# main.net
KiCad netlist of a schematic drawn in EAGLE
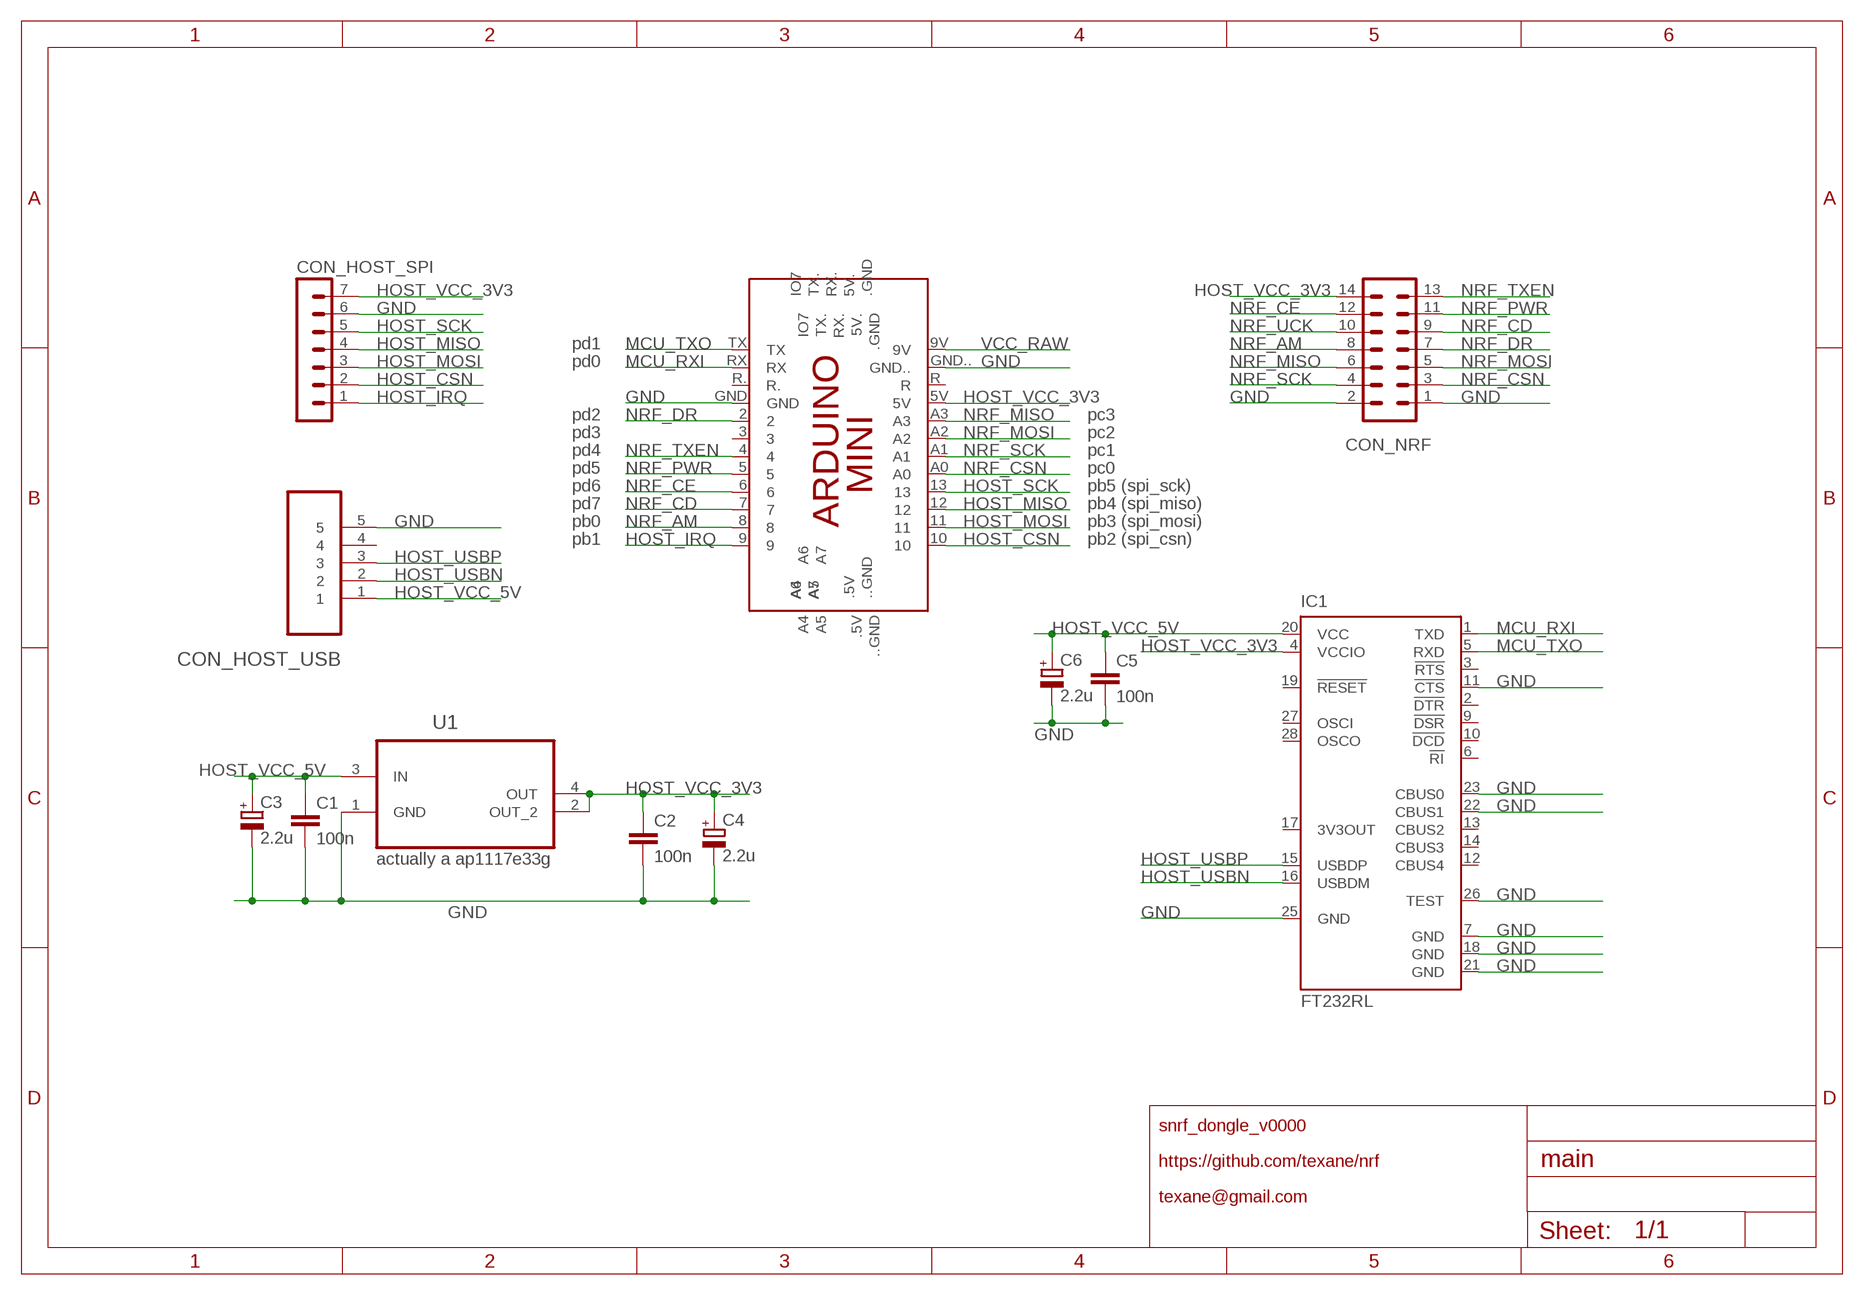
[diagram p0: schematic, sheet 1]

(export (version "E")
  (design (tool "Eeschema 10.0.6"))
  (components
    (comp (ref "C1")
      (value "100n")
      (footprint "eagle-import:C1206K")
      (libsource (lib "eagle-import") (part "C-EUC1206K"))
    )
    (comp (ref "C2")
      (value "100n")
      (footprint "eagle-import:C1206K")
      (libsource (lib "eagle-import") (part "C-EUC1206K"))
    )
    (comp (ref "C3")
      (value "2.2u")
      (footprint "eagle-import:A_3216-18W")
      (libsource (lib "eagle-import") (part "CPOL-EUA/3216-18W"))
    )
    (comp (ref "C4")
      (value "2.2u")
      (footprint "eagle-import:A_3216-18W")
      (libsource (lib "eagle-import") (part "CPOL-EUA/3216-18W"))
    )
    (comp (ref "C5")
      (value "100n")
      (footprint "eagle-import:C1206K")
      (libsource (lib "eagle-import") (part "C-EUC1206K"))
    )
    (comp (ref "C6")
      (value "2.2u")
      (footprint "eagle-import:A_3216-18W")
      (libsource (lib "eagle-import") (part "CPOL-EUA/3216-18W"))
    )
    (comp (ref "CON_HOST_SPI")
      (value "MA07-1")
      (footprint "eagle-import:MA07-1")
      (libsource (lib "eagle-import") (part "MA07-1"))
    )
    (comp (ref "CON_HOST_USB")
      (value "47346-0001")
      (footprint "eagle-import:MOLEX_47346-0001")
      (libsource (lib "eagle-import") (part "47346-0001"))
    )
    (comp (ref "CON_NRF")
      (value "MA07-2")
      (footprint "eagle-import:MA07-2")
      (libsource (lib "eagle-import") (part "MA07-2"))
    )
    (comp (ref "IC1")
      (value "FT232RL")
      (footprint "eagle-import:SSOP28")
      (libsource (lib "eagle-import") (part "FT232RL"))
    )
    (comp (ref "PCB1")
      (value "ARDUINO_MINI")
      (footprint "eagle-import:ARDUINO_MINI")
      (libsource (lib "eagle-import") (part "ARDUINO_MINI"))
    )
    (comp (ref "U1")
      (value "LDO33")
      (footprint "eagle-import:SOT230P700X180-4N")
      (fields (field (name "MPN") "ADP3338AKCZ-2.5RL7"))
      (libsource (lib "eagle-import") (part "ADP3338AKCZ-2.5RL7"))
    )
  )
  (nets
    (net (code "1") (name "/GND") (class "Default")
      (node (ref "C1") (pin "2") (pinfunction "2_2") (pintype "passive"))
      (node (ref "C2") (pin "2") (pinfunction "2_2") (pintype "passive"))
      (node (ref "C3") (pin "-") (pinfunction "-_-") (pintype "passive"))
      (node (ref "C4") (pin "-") (pinfunction "-_-") (pintype "passive"))
      (node (ref "C5") (pin "2") (pinfunction "2_2") (pintype "passive"))
      (node (ref "C6") (pin "-") (pinfunction "-_-") (pintype "passive"))
      (node (ref "CON_HOST_SPI") (pin "6") (pinfunction "6_6") (pintype "passive"))
      (node (ref "CON_HOST_USB") (pin "5") (pinfunction "5_5") (pintype "input"))
      (node (ref "CON_NRF") (pin "1") (pinfunction "1_1") (pintype "passive"))
      (node (ref "CON_NRF") (pin "2") (pinfunction "2_2") (pintype "passive"))
      (node (ref "IC1") (pin "11") (pinfunction "~{CTS}_11") (pintype "input"))
      (node (ref "IC1") (pin "18") (pinfunction "GND_18") (pintype "power_in"))
      (node (ref "IC1") (pin "21") (pinfunction "GND_21") (pintype "power_in"))
      (node (ref "IC1") (pin "22") (pinfunction "CBUS1_22") (pintype "bidirectional"))
      (node (ref "IC1") (pin "23") (pinfunction "CBUS0_23") (pintype "bidirectional"))
      (node (ref "IC1") (pin "25") (pinfunction "GND_25") (pintype "power_in"))
      (node (ref "IC1") (pin "26") (pinfunction "TEST_26") (pintype "input"))
      (node (ref "IC1") (pin "7") (pinfunction "GND_7") (pintype "power_in"))
      (node (ref "PCB1") (pin "GND") (pinfunction "GND_GND") (pintype "bidirectional"))
      (node (ref "PCB1") (pin "GND..") (pinfunction "GND.._GND..") (pintype "bidirectional"))
      (node (ref "U1") (pin "1") (pinfunction "GND_1") (pintype "passive"))
    )
    (net (code "2") (name "/HOST_CSN") (class "Default")
      (node (ref "CON_HOST_SPI") (pin "2") (pinfunction "2_2") (pintype "passive"))
      (node (ref "PCB1") (pin "10") (pinfunction "10_10") (pintype "bidirectional"))
    )
    (net (code "3") (name "/HOST_IRQ") (class "Default")
      (node (ref "CON_HOST_SPI") (pin "1") (pinfunction "1_1") (pintype "passive"))
      (node (ref "PCB1") (pin "9") (pinfunction "9_9") (pintype "bidirectional"))
    )
    (net (code "4") (name "/HOST_MISO") (class "Default")
      (node (ref "CON_HOST_SPI") (pin "4") (pinfunction "4_4") (pintype "passive"))
      (node (ref "PCB1") (pin "12") (pinfunction "12_12") (pintype "bidirectional"))
    )
    (net (code "5") (name "/HOST_MOSI") (class "Default")
      (node (ref "CON_HOST_SPI") (pin "3") (pinfunction "3_3") (pintype "passive"))
      (node (ref "PCB1") (pin "11") (pinfunction "11_11") (pintype "bidirectional"))
    )
    (net (code "6") (name "/HOST_SCK") (class "Default")
      (node (ref "CON_HOST_SPI") (pin "5") (pinfunction "5_5") (pintype "passive"))
      (node (ref "PCB1") (pin "13") (pinfunction "13_13") (pintype "bidirectional"))
    )
    (net (code "7") (name "/HOST_USBN") (class "Default")
      (node (ref "CON_HOST_USB") (pin "2") (pinfunction "2_2") (pintype "input"))
      (node (ref "IC1") (pin "16") (pinfunction "USBDM_16") (pintype "bidirectional"))
    )
    (net (code "8") (name "/HOST_USBP") (class "Default")
      (node (ref "CON_HOST_USB") (pin "3") (pinfunction "3_3") (pintype "input"))
      (node (ref "IC1") (pin "15") (pinfunction "USBDP_15") (pintype "bidirectional"))
    )
    (net (code "9") (name "/HOST_VCC_3V3") (class "Default")
      (node (ref "C2") (pin "1") (pinfunction "1_1") (pintype "passive"))
      (node (ref "C4") (pin "+") (pinfunction "+_+") (pintype "passive"))
      (node (ref "CON_HOST_SPI") (pin "7") (pinfunction "7_7") (pintype "passive"))
      (node (ref "CON_NRF") (pin "14") (pinfunction "14_14") (pintype "passive"))
      (node (ref "IC1") (pin "4") (pinfunction "VCCIO_4") (pintype "power_in"))
      (node (ref "PCB1") (pin "5V") (pinfunction "5V_5V") (pintype "bidirectional"))
      (node (ref "U1") (pin "2") (pinfunction "OUT_2_2") (pintype "output"))
      (node (ref "U1") (pin "4") (pinfunction "OUT_4") (pintype "output"))
    )
    (net (code "10") (name "/HOST_VCC_5V") (class "Default")
      (node (ref "C1") (pin "1") (pinfunction "1_1") (pintype "passive"))
      (node (ref "C3") (pin "+") (pinfunction "+_+") (pintype "passive"))
      (node (ref "C5") (pin "1") (pinfunction "1_1") (pintype "passive"))
      (node (ref "C6") (pin "+") (pinfunction "+_+") (pintype "passive"))
      (node (ref "CON_HOST_USB") (pin "1") (pinfunction "1_1") (pintype "input"))
      (node (ref "IC1") (pin "20") (pinfunction "VCC_20") (pintype "power_in"))
      (node (ref "U1") (pin "3") (pinfunction "IN_3") (pintype "input"))
    )
    (net (code "11") (name "/MCU_RXI") (class "Default")
      (node (ref "IC1") (pin "1") (pinfunction "TXD_1") (pintype "output"))
      (node (ref "PCB1") (pin "RX") (pinfunction "RX_RX") (pintype "bidirectional"))
    )
    (net (code "12") (name "/MCU_TXO") (class "Default")
      (node (ref "IC1") (pin "5") (pinfunction "RXD_5") (pintype "input"))
      (node (ref "PCB1") (pin "TX") (pinfunction "TX_TX") (pintype "bidirectional"))
    )
    (net (code "13") (name "/NRF_AM") (class "Default")
      (node (ref "CON_NRF") (pin "8") (pinfunction "8_8") (pintype "passive"))
      (node (ref "PCB1") (pin "8") (pinfunction "8_8") (pintype "bidirectional"))
    )
    (net (code "14") (name "/NRF_CD") (class "Default")
      (node (ref "CON_NRF") (pin "9") (pinfunction "9_9") (pintype "passive"))
      (node (ref "PCB1") (pin "7") (pinfunction "7_7") (pintype "bidirectional"))
    )
    (net (code "15") (name "/NRF_CE") (class "Default")
      (node (ref "CON_NRF") (pin "12") (pinfunction "12_12") (pintype "passive"))
      (node (ref "PCB1") (pin "6") (pinfunction "6_6") (pintype "bidirectional"))
    )
    (net (code "16") (name "/NRF_CSN") (class "Default")
      (node (ref "CON_NRF") (pin "3") (pinfunction "3_3") (pintype "passive"))
      (node (ref "PCB1") (pin "A0") (pinfunction "A0_A0") (pintype "bidirectional"))
    )
    (net (code "17") (name "/NRF_DR") (class "Default")
      (node (ref "CON_NRF") (pin "7") (pinfunction "7_7") (pintype "passive"))
      (node (ref "PCB1") (pin "2") (pinfunction "2_2") (pintype "bidirectional"))
    )
    (net (code "18") (name "/NRF_MISO") (class "Default")
      (node (ref "CON_NRF") (pin "6") (pinfunction "6_6") (pintype "passive"))
      (node (ref "PCB1") (pin "A3") (pinfunction "A3_A3") (pintype "bidirectional"))
    )
    (net (code "19") (name "/NRF_MOSI") (class "Default")
      (node (ref "CON_NRF") (pin "5") (pinfunction "5_5") (pintype "passive"))
      (node (ref "PCB1") (pin "A2") (pinfunction "A2_A2") (pintype "bidirectional"))
    )
    (net (code "20") (name "/NRF_PWR") (class "Default")
      (node (ref "CON_NRF") (pin "11") (pinfunction "11_11") (pintype "passive"))
      (node (ref "PCB1") (pin "5") (pinfunction "5_5") (pintype "bidirectional"))
    )
    (net (code "21") (name "/NRF_SCK") (class "Default")
      (node (ref "CON_NRF") (pin "4") (pinfunction "4_4") (pintype "passive"))
      (node (ref "PCB1") (pin "A1") (pinfunction "A1_A1") (pintype "bidirectional"))
    )
    (net (code "22") (name "/NRF_TXEN") (class "Default")
      (node (ref "CON_NRF") (pin "13") (pinfunction "13_13") (pintype "passive"))
      (node (ref "PCB1") (pin "4") (pinfunction "4_4") (pintype "bidirectional"))
    )
    (net (code "23") (name "/NRF_UCK") (class "Default")
      (node (ref "CON_NRF") (pin "10") (pinfunction "10_10") (pintype "passive"))
    )
    (net (code "24") (name "/VCC_RAW") (class "Default")
      (node (ref "PCB1") (pin "9V") (pinfunction "9V_9V") (pintype "bidirectional"))
    )
    (net (code "25") (name "unconnected-(CON_HOST_USB-Pad4)") (class "Default")
      (node (ref "CON_HOST_USB") (pin "4") (pinfunction "4_4") (pintype "input"))
    )
    (net (code "26") (name "unconnected-(IC1-3V3OUT-Pad17)") (class "Default")
      (node (ref "IC1") (pin "17") (pinfunction "3V3OUT_17") (pintype "output"))
    )
    (net (code "27") (name "unconnected-(IC1-CBUS2-Pad13)") (class "Default")
      (node (ref "IC1") (pin "13") (pinfunction "CBUS2_13") (pintype "bidirectional"))
    )
    (net (code "28") (name "unconnected-(IC1-CBUS3-Pad14)") (class "Default")
      (node (ref "IC1") (pin "14") (pinfunction "CBUS3_14") (pintype "bidirectional"))
    )
    (net (code "29") (name "unconnected-(IC1-CBUS4-Pad12)") (class "Default")
      (node (ref "IC1") (pin "12") (pinfunction "CBUS4_12") (pintype "bidirectional"))
    )
    (net (code "30") (name "unconnected-(IC1-OSCI-Pad27)") (class "Default")
      (node (ref "IC1") (pin "27") (pinfunction "OSCI_27") (pintype "input"))
    )
    (net (code "31") (name "unconnected-(IC1-OSCO-Pad28)") (class "Default")
      (node (ref "IC1") (pin "28") (pinfunction "OSCO_28") (pintype "output"))
    )
    (net (code "32") (name "unconnected-(IC1-~{DCD}-Pad10)") (class "Default")
      (node (ref "IC1") (pin "10") (pinfunction "~{DCD}_10") (pintype "input"))
    )
    (net (code "33") (name "unconnected-(IC1-~{DSR}-Pad9)") (class "Default")
      (node (ref "IC1") (pin "9") (pinfunction "~{DSR}_9") (pintype "input"))
    )
    (net (code "34") (name "unconnected-(IC1-~{DTR}-Pad2)") (class "Default")
      (node (ref "IC1") (pin "2") (pinfunction "~{DTR}_2") (pintype "output"))
    )
    (net (code "35") (name "unconnected-(IC1-~{RESET}-Pad19)") (class "Default")
      (node (ref "IC1") (pin "19") (pinfunction "~{RESET}_19") (pintype "input"))
    )
    (net (code "36") (name "unconnected-(IC1-~{RI}-Pad6)") (class "Default")
      (node (ref "IC1") (pin "6") (pinfunction "~{RI}_6") (pintype "input"))
    )
    (net (code "37") (name "unconnected-(IC1-~{RTS}-Pad3)") (class "Default")
      (node (ref "IC1") (pin "3") (pinfunction "~{RTS}_3") (pintype "output"))
    )
    (net (code "38") (name "unconnected-(PCB1-Pad..GND)") (class "Default")
      (node (ref "PCB1") (pin "..GND") (pinfunction "..GND_..GND") (pintype "bidirectional"))
    )
    (net (code "39") (name "unconnected-(PCB1-Pad.5V)") (class "Default")
      (node (ref "PCB1") (pin ".5V") (pinfunction ".5V_.5V") (pintype "bidirectional"))
    )
    (net (code "40") (name "unconnected-(PCB1-Pad.GND)") (class "Default")
      (node (ref "PCB1") (pin ".GND") (pinfunction ".GND_.GND") (pintype "bidirectional"))
    )
    (net (code "41") (name "unconnected-(PCB1-Pad3)") (class "Default")
      (node (ref "PCB1") (pin "3") (pinfunction "3_3") (pintype "bidirectional"))
    )
    (net (code "42") (name "unconnected-(PCB1-Pad5V.)") (class "Default")
      (node (ref "PCB1") (pin "5V.") (pinfunction "5V._5V.") (pintype "bidirectional"))
    )
    (net (code "43") (name "unconnected-(PCB1-PadA4)") (class "Default")
      (node (ref "PCB1") (pin "A4") (pinfunction "A4_A4") (pintype "bidirectional"))
    )
    (net (code "44") (name "unconnected-(PCB1-PadA5)") (class "Default")
      (node (ref "PCB1") (pin "A5") (pinfunction "A5_A5") (pintype "bidirectional"))
    )
    (net (code "45") (name "unconnected-(PCB1-PadA6)") (class "Default")
      (node (ref "PCB1") (pin "A6") (pinfunction "A6_A6") (pintype "bidirectional"))
    )
    (net (code "46") (name "unconnected-(PCB1-PadA7)") (class "Default")
      (node (ref "PCB1") (pin "A7") (pinfunction "A7_A7") (pintype "bidirectional"))
    )
    (net (code "47") (name "unconnected-(PCB1-PadIO7)") (class "Default")
      (node (ref "PCB1") (pin "IO7") (pinfunction "IO7_IO7") (pintype "bidirectional"))
    )
    (net (code "48") (name "unconnected-(PCB1-PadR)") (class "Default")
      (node (ref "PCB1") (pin "R") (pinfunction "R_R") (pintype "bidirectional"))
    )
    (net (code "49") (name "unconnected-(PCB1-PadR.)") (class "Default")
      (node (ref "PCB1") (pin "R.") (pinfunction "R._R.") (pintype "bidirectional"))
    )
    (net (code "50") (name "unconnected-(PCB1-PadRX.)") (class "Default")
      (node (ref "PCB1") (pin "RX.") (pinfunction "RX._RX.") (pintype "bidirectional"))
    )
    (net (code "51") (name "unconnected-(PCB1-PadTX.)") (class "Default")
      (node (ref "PCB1") (pin "TX.") (pinfunction "TX._TX.") (pintype "bidirectional"))
    )
  )
)
